# Adafruit_USB_Serial_Char_LCD.net
KiCad netlist of a schematic drawn in EAGLE
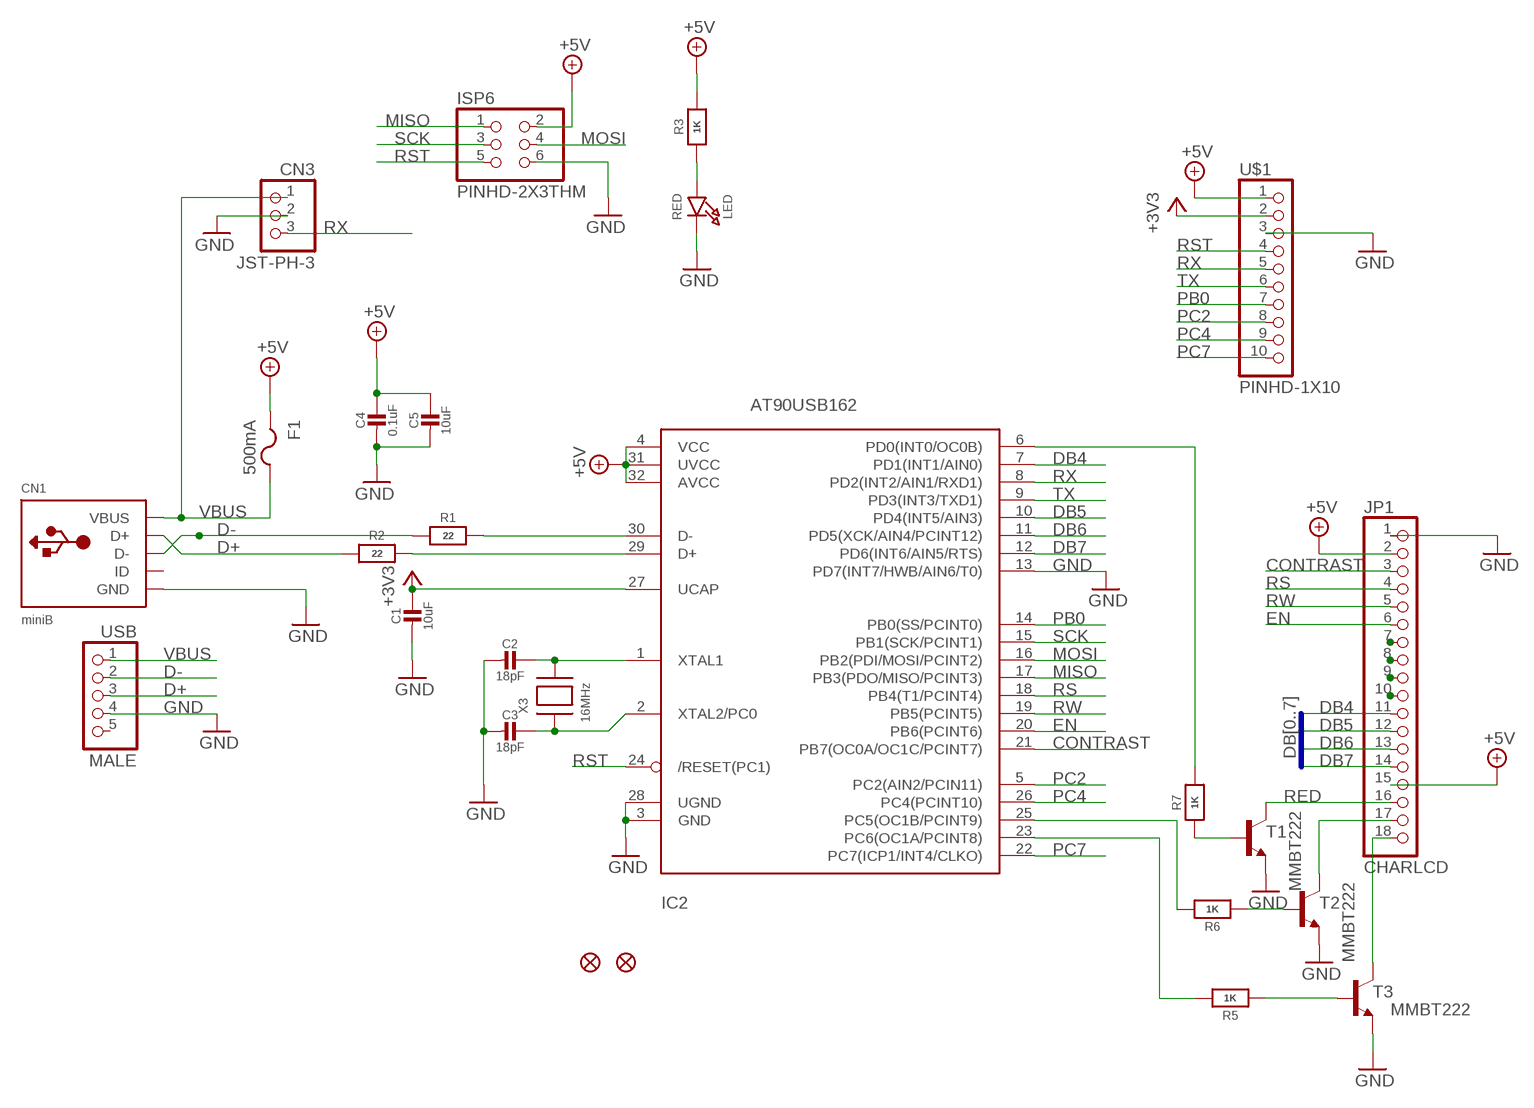
[diagram p0: schematic, sheet 1]

(export (version "E")
  (design (tool "Eeschema 10.0.6"))
  (components
    (comp (ref "C1")
      (value "10uF")
      (footprint "eagle-import:0805-NO")
      (libsource (lib "eagle-import") (part "CAP_CERAMIC0805-NOOUTLINE"))
    )
    (comp (ref "C2")
      (value "18pF")
      (footprint "eagle-import:0805-NO")
      (libsource (lib "eagle-import") (part "CAP_CERAMIC0805-NOOUTLINE"))
    )
    (comp (ref "C3")
      (value "18pF")
      (footprint "eagle-import:0805-NO")
      (libsource (lib "eagle-import") (part "CAP_CERAMIC0805-NOOUTLINE"))
    )
    (comp (ref "C4")
      (value "0.1uF")
      (footprint "eagle-import:0805-NO")
      (libsource (lib "eagle-import") (part "CAP_CERAMIC0805-NOOUTLINE"))
    )
    (comp (ref "C5")
      (value "10uF")
      (footprint "eagle-import:0805-NO")
      (libsource (lib "eagle-import") (part "CAP_CERAMIC0805-NOOUTLINE"))
    )
    (comp (ref "CN1")
      (value "miniB")
      (footprint "eagle-import:USB-MINIB_LARGER")
      (libsource (lib "eagle-import") (part "USBMINIBLARGE"))
    )
    (comp (ref "CN3")
      (value "JST-PH-3")
      (footprint "eagle-import:JSTPH3")
      (libsource (lib "eagle-import") (part "JST_3PIN"))
    )
    (comp (ref "F1")
      (value "500mA")
      (footprint "eagle-import:R1206")
      (libsource (lib "eagle-import") (part "PTCFUSE-1206"))
    )
    (comp (ref "FID1")
      (value "FIDUCIAL1X2.5")
      (footprint "eagle-import:FIDUCIAL-1X2.5")
      (libsource (lib "eagle-import") (part "FIDUCIAL1X2.5"))
    )
    (comp (ref "FID2")
      (value "FIDUCIAL1X2.5")
      (footprint "eagle-import:FIDUCIAL-1X2.5")
      (libsource (lib "eagle-import") (part "FIDUCIAL1X2.5"))
    )
    (comp (ref "IC2")
      (value "AT90USB162")
      (footprint "eagle-import:TQFP32-08")
      (libsource (lib "eagle-import") (part "ATMEGA32U2-TQFP"))
    )
    (comp (ref "ISP6")
      (value "PINHD-2X3THM")
      (footprint "eagle-import:ISP6")
      (libsource (lib "eagle-import") (part "PINHD-2X3THM"))
    )
    (comp (ref "JP1")
      (value "CHARLCD")
      (footprint "eagle-import:1X18-BIG")
      (libsource (lib "eagle-import") (part "PINHD-1X18-BIG"))
    )
    (comp (ref "LED")
      (value "RED")
      (footprint "eagle-import:CHIPLED_0805_NOOUTLINE")
      (libsource (lib "eagle-import") (part "LED0805_NOOUTLINE"))
    )
    (comp (ref "R1")
      (value "22")
      (footprint "eagle-import:0805-NO")
      (libsource (lib "eagle-import") (part "RESISTOR0805_NOOUTLINE"))
    )
    (comp (ref "R2")
      (value "22")
      (footprint "eagle-import:0805-NO")
      (libsource (lib "eagle-import") (part "RESISTOR0805_NOOUTLINE"))
    )
    (comp (ref "R3")
      (value "1K")
      (footprint "eagle-import:0805-NO")
      (libsource (lib "eagle-import") (part "RESISTOR0805_NOOUTLINE"))
    )
    (comp (ref "R5")
      (value "1K")
      (footprint "eagle-import:0805-NO")
      (libsource (lib "eagle-import") (part "RESISTOR0805_NOOUTLINE"))
    )
    (comp (ref "R6")
      (value "1K")
      (footprint "eagle-import:0805-NO")
      (libsource (lib "eagle-import") (part "RESISTOR0805_NOOUTLINE"))
    )
    (comp (ref "R7")
      (value "1K")
      (footprint "eagle-import:0805-NO")
      (libsource (lib "eagle-import") (part "RESISTOR0805_NOOUTLINE"))
    )
    (comp (ref "T1")
      (value "MMBT222")
      (footprint "eagle-import:SOT23-BEC")
      (libsource (lib "eagle-import") (part "-NPN-SOT23-BECMMBT2222ALT1"))
    )
    (comp (ref "T2")
      (value "MMBT222")
      (footprint "eagle-import:SOT23-BEC")
      (libsource (lib "eagle-import") (part "-NPN-SOT23-BECMMBT2222ALT1"))
    )
    (comp (ref "T3")
      (value "MMBT222")
      (footprint "eagle-import:SOT23-BEC")
      (libsource (lib "eagle-import") (part "-NPN-SOT23-BECMMBT2222ALT1"))
    )
    (comp (ref "U$1")
      (value "PINHD-1X10")
      (footprint "eagle-import:1X10-BIG")
      (libsource (lib "eagle-import") (part "PINHD-1X10"))
    )
    (comp (ref "USB")
      (value "MALE")
      (footprint "eagle-import:1X05")
      (libsource (lib "eagle-import") (part "PINHD-1X5"))
    )
    (comp (ref "X3")
      (value "16MHz")
      (footprint "eagle-import:NX5032")
      (libsource (lib "eagle-import") (part "XTALNX5032"))
    )
  )
  (nets
    (net (code "5") (name "+3V3") (class "Default")
      (node (ref "C1") (pin "1") (pinfunction "1_1") (pintype "passive"))
      (node (ref "IC2") (pin "27") (pinfunction "UCAP_27") (pintype "bidirectional"))
      (node (ref "U$1") (pin "2") (pinfunction "2_2") (pintype "passive"))
    )
    (net (code "6") (name "+5V") (class "Default")
      (node (ref "C4") (pin "1") (pinfunction "1_1") (pintype "passive"))
      (node (ref "C5") (pin "1") (pinfunction "1_1") (pintype "passive"))
      (node (ref "F1") (pin "1") (pinfunction "1_1") (pintype "passive"))
      (node (ref "IC2") (pin "31") (pinfunction "UVCC_31") (pintype "bidirectional"))
      (node (ref "IC2") (pin "32") (pinfunction "AVCC_32") (pintype "bidirectional"))
      (node (ref "IC2") (pin "4") (pinfunction "VCC_4") (pintype "bidirectional"))
      (node (ref "ISP6") (pin "2") (pinfunction "2_2") (pintype "passive"))
      (node (ref "JP1") (pin "15") (pinfunction "15_15") (pintype "passive"))
      (node (ref "JP1") (pin "2") (pinfunction "2_2") (pintype "passive"))
      (node (ref "R3") (pin "2") (pinfunction "2_2") (pintype "passive"))
      (node (ref "U$1") (pin "1") (pinfunction "1_1") (pintype "passive"))
    )
    (net (code "7") (name "/CONTRAST") (class "Default")
      (node (ref "IC2") (pin "21") (pinfunction "PB7(OC0A/OC1C/PCINT7)_21") (pintype "bidirectional"))
      (node (ref "JP1") (pin "3") (pinfunction "3_3") (pintype "passive"))
    )
    (net (code "8") (name "/D+") (class "Default")
      (node (ref "CN1") (pin "D+") (pinfunction "D+_D+") (pintype "bidirectional"))
      (node (ref "R2") (pin "1") (pinfunction "1_1") (pintype "passive"))
      (node (ref "USB") (pin "3") (pinfunction "3_3") (pintype "passive"))
    )
    (net (code "9") (name "/D-") (class "Default")
      (node (ref "CN1") (pin "D-") (pinfunction "D-_D-") (pintype "bidirectional"))
      (node (ref "R1") (pin "1") (pinfunction "1_1") (pintype "passive"))
      (node (ref "USB") (pin "2") (pinfunction "2_2") (pintype "passive"))
    )
    (net (code "10") (name "/DB4") (class "Default")
      (node (ref "IC2") (pin "7") (pinfunction "PD1(INT1/AIN0)_7") (pintype "bidirectional"))
      (node (ref "JP1") (pin "11") (pinfunction "11_11") (pintype "passive"))
    )
    (net (code "11") (name "/DB5") (class "Default")
      (node (ref "IC2") (pin "10") (pinfunction "PD4(INT5/AIN3)_10") (pintype "bidirectional"))
      (node (ref "JP1") (pin "12") (pinfunction "12_12") (pintype "passive"))
    )
    (net (code "12") (name "/DB6") (class "Default")
      (node (ref "IC2") (pin "11") (pinfunction "PD5(XCK/AIN4/PCINT12)_11") (pintype "bidirectional"))
      (node (ref "JP1") (pin "13") (pinfunction "13_13") (pintype "passive"))
    )
    (net (code "13") (name "/DB7") (class "Default")
      (node (ref "IC2") (pin "12") (pinfunction "PD6(INT6/AIN5/RTS)_12") (pintype "bidirectional"))
      (node (ref "JP1") (pin "14") (pinfunction "14_14") (pintype "passive"))
    )
    (net (code "15") (name "/EN") (class "Default")
      (node (ref "IC2") (pin "20") (pinfunction "PB6(PCINT6)_20") (pintype "bidirectional"))
      (node (ref "JP1") (pin "6") (pinfunction "6_6") (pintype "passive"))
    )
    (net (code "16") (name "/MISO") (class "Default")
      (node (ref "IC2") (pin "17") (pinfunction "PB3(PDO/MISO/PCINT3)_17") (pintype "bidirectional"))
      (node (ref "ISP6") (pin "1") (pinfunction "1_1") (pintype "passive"))
    )
    (net (code "17") (name "/MOSI") (class "Default")
      (node (ref "IC2") (pin "16") (pinfunction "PB2(PDI/MOSI/PCINT2)_16") (pintype "bidirectional"))
      (node (ref "ISP6") (pin "4") (pinfunction "4_4") (pintype "passive"))
    )
    (net (code "18") (name "/PB0") (class "Default")
      (node (ref "IC2") (pin "14") (pinfunction "PB0(SS/PCINT0)_14") (pintype "bidirectional"))
      (node (ref "U$1") (pin "7") (pinfunction "7_7") (pintype "passive"))
    )
    (net (code "19") (name "/PC2") (class "Default")
      (node (ref "IC2") (pin "5") (pinfunction "PC2(AIN2/PCIN11)_5") (pintype "bidirectional"))
      (node (ref "U$1") (pin "8") (pinfunction "8_8") (pintype "passive"))
    )
    (net (code "20") (name "/PC4") (class "Default")
      (node (ref "IC2") (pin "26") (pinfunction "PC4(PCINT10)_26") (pintype "bidirectional"))
      (node (ref "U$1") (pin "9") (pinfunction "9_9") (pintype "passive"))
    )
    (net (code "21") (name "/PC7") (class "Default")
      (node (ref "IC2") (pin "22") (pinfunction "PC7(ICP1/INT4/CLKO)_22") (pintype "bidirectional"))
      (node (ref "U$1") (pin "10") (pinfunction "10_10") (pintype "passive"))
    )
    (net (code "22") (name "/RED") (class "Default")
      (node (ref "JP1") (pin "16") (pinfunction "16_16") (pintype "passive"))
      (node (ref "T1") (pin "C") (pinfunction "C_C") (pintype "passive"))
    )
    (net (code "23") (name "/RS") (class "Default")
      (node (ref "IC2") (pin "18") (pinfunction "PB4(T1/PCINT4)_18") (pintype "bidirectional"))
      (node (ref "JP1") (pin "4") (pinfunction "4_4") (pintype "passive"))
    )
    (net (code "24") (name "/RST") (class "Default")
      (node (ref "IC2") (pin "24") (pinfunction "/RESET(PC1)_24") (pintype "bidirectional"))
      (node (ref "ISP6") (pin "5") (pinfunction "5_5") (pintype "passive"))
      (node (ref "U$1") (pin "4") (pinfunction "4_4") (pintype "passive"))
    )
    (net (code "25") (name "/RW") (class "Default")
      (node (ref "IC2") (pin "19") (pinfunction "PB5(PCINT5)_19") (pintype "bidirectional"))
      (node (ref "JP1") (pin "5") (pinfunction "5_5") (pintype "passive"))
    )
    (net (code "26") (name "/RX") (class "Default")
      (node (ref "CN3") (pin "3") (pinfunction "3_3") (pintype "passive"))
      (node (ref "IC2") (pin "8") (pinfunction "PD2(INT2/AIN1/RXD1)_8") (pintype "bidirectional"))
      (node (ref "U$1") (pin "5") (pinfunction "5_5") (pintype "passive"))
    )
    (net (code "27") (name "/SCK") (class "Default")
      (node (ref "IC2") (pin "15") (pinfunction "PB1(SCK/PCINT1)_15") (pintype "bidirectional"))
      (node (ref "ISP6") (pin "3") (pinfunction "3_3") (pintype "passive"))
    )
    (net (code "28") (name "/TX") (class "Default")
      (node (ref "IC2") (pin "9") (pinfunction "PD3(INT3/TXD1)_9") (pintype "bidirectional"))
      (node (ref "U$1") (pin "6") (pinfunction "6_6") (pintype "passive"))
    )
    (net (code "29") (name "/VBUS") (class "Default")
      (node (ref "CN1") (pin "VBUS") (pinfunction "VBUS_VBUS") (pintype "power_in"))
      (node (ref "CN3") (pin "1") (pinfunction "1_1") (pintype "passive"))
      (node (ref "F1") (pin "2") (pinfunction "2_2") (pintype "passive"))
      (node (ref "USB") (pin "1") (pinfunction "1_1") (pintype "passive"))
    )
    (net (code "30") (name "GND") (class "Default")
      (node (ref "C1") (pin "2") (pinfunction "2_2") (pintype "passive"))
      (node (ref "C2") (pin "2") (pinfunction "2_2") (pintype "passive"))
      (node (ref "C3") (pin "2") (pinfunction "2_2") (pintype "passive"))
      (node (ref "C4") (pin "2") (pinfunction "2_2") (pintype "passive"))
      (node (ref "C5") (pin "2") (pinfunction "2_2") (pintype "passive"))
      (node (ref "CN1") (pin "GND") (pinfunction "GND_GND") (pintype "power_in"))
      (node (ref "CN3") (pin "2") (pinfunction "2_2") (pintype "passive"))
      (node (ref "IC2") (pin "13") (pinfunction "PD7(INT7/HWB/AIN6/T0)_13") (pintype "bidirectional"))
      (node (ref "IC2") (pin "28") (pinfunction "UGND_28") (pintype "bidirectional"))
      (node (ref "IC2") (pin "3") (pinfunction "GND_3") (pintype "bidirectional"))
      (node (ref "ISP6") (pin "6") (pinfunction "6_6") (pintype "passive"))
      (node (ref "JP1") (pin "1") (pinfunction "1_1") (pintype "passive"))
      (node (ref "LED") (pin "C") (pinfunction "C_C") (pintype "passive"))
      (node (ref "T1") (pin "E") (pinfunction "E_E") (pintype "passive"))
      (node (ref "T2") (pin "E") (pinfunction "E_E") (pintype "passive"))
      (node (ref "T3") (pin "E") (pinfunction "E_E") (pintype "passive"))
      (node (ref "U$1") (pin "3") (pinfunction "3_3") (pintype "passive"))
      (node (ref "USB") (pin "4") (pinfunction "4_4") (pintype "passive"))
    )
    (net (code "31") (name "Net-(IC2-D+)") (class "Default")
      (node (ref "IC2") (pin "29") (pinfunction "D+_29") (pintype "bidirectional"))
      (node (ref "R2") (pin "2") (pinfunction "2_2") (pintype "passive"))
    )
    (net (code "32") (name "Net-(IC2-D-)") (class "Default")
      (node (ref "IC2") (pin "30") (pinfunction "D-_30") (pintype "bidirectional"))
      (node (ref "R1") (pin "2") (pinfunction "2_2") (pintype "passive"))
    )
    (net (code "33") (name "Net-(IC2-PC5(OC1B{slash}PCINT9))") (class "Default")
      (node (ref "IC2") (pin "25") (pinfunction "PC5(OC1B/PCINT9)_25") (pintype "bidirectional"))
      (node (ref "R6") (pin "2") (pinfunction "2_2") (pintype "passive"))
    )
    (net (code "34") (name "Net-(IC2-PC6(OC1A{slash}PCINT8))") (class "Default")
      (node (ref "IC2") (pin "23") (pinfunction "PC6(OC1A/PCINT8)_23") (pintype "bidirectional"))
      (node (ref "R5") (pin "2") (pinfunction "2_2") (pintype "passive"))
    )
    (net (code "35") (name "Net-(IC2-PD0(INT0{slash}OC0B))") (class "Default")
      (node (ref "IC2") (pin "6") (pinfunction "PD0(INT0/OC0B)_6") (pintype "bidirectional"))
      (node (ref "R7") (pin "2") (pinfunction "2_2") (pintype "passive"))
    )
    (net (code "36") (name "Net-(IC2-XTAL1)") (class "Default")
      (node (ref "C2") (pin "1") (pinfunction "1_1") (pintype "passive"))
      (node (ref "IC2") (pin "1") (pinfunction "XTAL1_1") (pintype "bidirectional"))
      (node (ref "X3") (pin "P$2") (pinfunction "P$2_P$2") (pintype "bidirectional"))
    )
    (net (code "37") (name "Net-(IC2-XTAL2{slash}PC0)") (class "Default")
      (node (ref "C3") (pin "1") (pinfunction "1_1") (pintype "passive"))
      (node (ref "IC2") (pin "2") (pinfunction "XTAL2/PC0_2") (pintype "bidirectional"))
      (node (ref "X3") (pin "P$1") (pinfunction "P$1_P$1") (pintype "bidirectional"))
    )
    (net (code "38") (name "Net-(JP1-Pad17)") (class "Default")
      (node (ref "JP1") (pin "17") (pinfunction "17_17") (pintype "passive"))
      (node (ref "T2") (pin "C") (pinfunction "C_C") (pintype "passive"))
    )
    (net (code "39") (name "Net-(JP1-Pad18)") (class "Default")
      (node (ref "JP1") (pin "18") (pinfunction "18_18") (pintype "passive"))
      (node (ref "T3") (pin "C") (pinfunction "C_C") (pintype "passive"))
    )
    (net (code "40") (name "Net-(LED-PadA)") (class "Default")
      (node (ref "LED") (pin "A") (pinfunction "A_A") (pintype "passive"))
      (node (ref "R3") (pin "1") (pinfunction "1_1") (pintype "passive"))
    )
    (net (code "41") (name "Net-(R5-Pad1)") (class "Default")
      (node (ref "R5") (pin "1") (pinfunction "1_1") (pintype "passive"))
      (node (ref "T3") (pin "B") (pinfunction "B_B") (pintype "passive"))
    )
    (net (code "42") (name "Net-(R6-Pad1)") (class "Default")
      (node (ref "R6") (pin "1") (pinfunction "1_1") (pintype "passive"))
      (node (ref "T2") (pin "B") (pinfunction "B_B") (pintype "passive"))
    )
    (net (code "43") (name "Net-(R7-Pad1)") (class "Default")
      (node (ref "R7") (pin "1") (pinfunction "1_1") (pintype "passive"))
      (node (ref "T1") (pin "B") (pinfunction "B_B") (pintype "passive"))
    )
    (net (code "44") (name "unconnected-(CN1-PadID)") (class "Default")
      (node (ref "CN1") (pin "ID") (pinfunction "ID_ID") (pintype "bidirectional"))
    )
    (net (code "45") (name "unconnected-(JP1-Pad7)") (class "Default")
      (node (ref "JP1") (pin "7") (pinfunction "7_7") (pintype "passive"))
    )
    (net (code "46") (name "unconnected-(JP1-Pad8)") (class "Default")
      (node (ref "JP1") (pin "8") (pinfunction "8_8") (pintype "passive"))
    )
    (net (code "47") (name "unconnected-(JP1-Pad9)") (class "Default")
      (node (ref "JP1") (pin "9") (pinfunction "9_9") (pintype "passive"))
    )
    (net (code "48") (name "unconnected-(JP1-Pad10)") (class "Default")
      (node (ref "JP1") (pin "10") (pinfunction "10_10") (pintype "passive"))
    )
    (net (code "49") (name "unconnected-(USB-Pad5)") (class "Default")
      (node (ref "USB") (pin "5") (pinfunction "5_5") (pintype "passive"))
    )
  )
)
